# main_6.net
KiCad netlist of a schematic drawn in Altium Designer
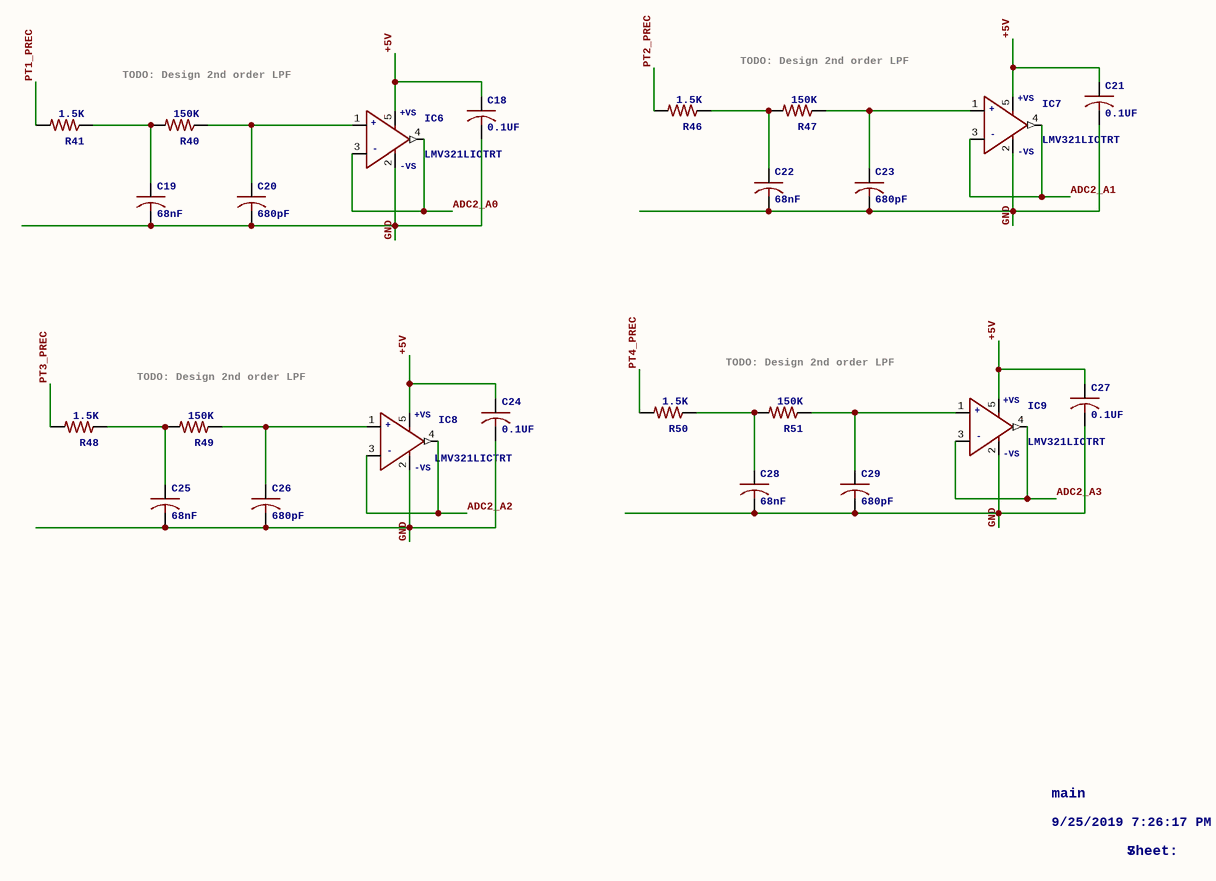
[diagram p0: main_6.SchDoc]

(export (version "E")
  (design (tool "Eeschema 10.0.6"))
  (components
    (comp (ref "C18")
      (value "0.1UF")
      (footprint "C0805")
      (description "CAPACITOR, American symbol")
      (libsource (lib "rcl") (part "C-USC0805"))
    )
    (comp (ref "C19")
      (value "68nF")
      (footprint "C0805")
      (description "CAPACITOR, American symbol")
      (libsource (lib "rcl") (part "C-USC0805"))
    )
    (comp (ref "C20")
      (value "680pF")
      (footprint "C0805")
      (description "CAPACITOR, American symbol")
      (libsource (lib "rcl") (part "C-USC0805"))
    )
    (comp (ref "C21")
      (value "0.1UF")
      (footprint "C0805")
      (description "CAPACITOR, American symbol")
      (libsource (lib "rcl") (part "C-USC0805"))
    )
    (comp (ref "C22")
      (value "68nF")
      (footprint "C0805")
      (description "CAPACITOR, American symbol")
      (libsource (lib "rcl") (part "C-USC0805"))
    )
    (comp (ref "C23")
      (value "680pF")
      (footprint "C0805")
      (description "CAPACITOR, American symbol")
      (libsource (lib "rcl") (part "C-USC0805"))
    )
    (comp (ref "C24")
      (value "0.1UF")
      (footprint "C0805")
      (description "CAPACITOR, American symbol")
      (libsource (lib "rcl") (part "C-USC0805"))
    )
    (comp (ref "C25")
      (value "68nF")
      (footprint "C0805")
      (description "CAPACITOR, American symbol")
      (libsource (lib "rcl") (part "C-USC0805"))
    )
    (comp (ref "C26")
      (value "680pF")
      (footprint "C0805")
      (description "CAPACITOR, American symbol")
      (libsource (lib "rcl") (part "C-USC0805"))
    )
    (comp (ref "C27")
      (value "0.1UF")
      (footprint "C0805")
      (description "CAPACITOR, American symbol")
      (libsource (lib "rcl") (part "C-USC0805"))
    )
    (comp (ref "C28")
      (value "68nF")
      (footprint "C0805")
      (description "CAPACITOR, American symbol")
      (libsource (lib "rcl") (part "C-USC0805"))
    )
    (comp (ref "C29")
      (value "680pF")
      (footprint "C0805")
      (description "CAPACITOR, American symbol")
      (libsource (lib "rcl") (part "C-USC0805"))
    )
    (comp (ref "IC6")
      (value "LMV321LICTRT")
      (footprint "SOT23-5")
      (fields
        (field (name "MF") "ALTERA CORPORATION")
        (field (name "MPN") "AD8065ARTZ-REEL7")
        (field (name "+") "+")
        (field (name "-") "-")
        (field (name "+VS") "+VS")
        (field (name "-VS") "-VS")
        (field (name "LIBRARYNAME") "st-microelectronics-extra")
      )
      (libsource (lib "st-microelectronics-extra") (part "LMV321LICTRT"))
    )
    (comp (ref "IC7")
      (value "LMV321LICTRT")
      (footprint "SOT23-5")
      (fields
        (field (name "MF") "ALTERA CORPORATION")
        (field (name "MPN") "AD8065ARTZ-REEL7")
        (field (name "+") "+")
        (field (name "-") "-")
        (field (name "+VS") "+VS")
        (field (name "-VS") "-VS")
        (field (name "LIBRARYNAME") "st-microelectronics-extra")
      )
      (libsource (lib "st-microelectronics-extra") (part "LMV321LICTRT"))
    )
    (comp (ref "IC8")
      (value "LMV321LICTRT")
      (footprint "SOT23-5")
      (fields
        (field (name "MF") "ALTERA CORPORATION")
        (field (name "MPN") "AD8065ARTZ-REEL7")
        (field (name "+") "+")
        (field (name "-") "-")
        (field (name "+VS") "+VS")
        (field (name "-VS") "-VS")
        (field (name "LIBRARYNAME") "st-microelectronics-extra")
      )
      (libsource (lib "st-microelectronics-extra") (part "LMV321LICTRT"))
    )
    (comp (ref "IC9")
      (value "LMV321LICTRT")
      (footprint "SOT23-5")
      (fields
        (field (name "MF") "ALTERA CORPORATION")
        (field (name "MPN") "AD8065ARTZ-REEL7")
        (field (name "+") "+")
        (field (name "-") "-")
        (field (name "+VS") "+VS")
        (field (name "-VS") "-VS")
        (field (name "LIBRARYNAME") "st-microelectronics-extra")
      )
      (libsource (lib "st-microelectronics-extra") (part "LMV321LICTRT"))
    )
    (comp (ref "R40")
      (value "150K")
      (footprint "R0805")
      (description "RESISTOR, American symbol")
      (libsource (lib "rcl") (part "R-US_R0805"))
    )
    (comp (ref "R41")
      (value "1.5K")
      (footprint "R0805")
      (description "RESISTOR, American symbol")
      (libsource (lib "rcl") (part "R-US_R0805"))
    )
    (comp (ref "R46")
      (value "1.5K")
      (footprint "R0805")
      (description "RESISTOR, American symbol")
      (libsource (lib "rcl") (part "R-US_R0805"))
    )
    (comp (ref "R47")
      (value "150K")
      (footprint "R0805")
      (description "RESISTOR, American symbol")
      (libsource (lib "rcl") (part "R-US_R0805"))
    )
    (comp (ref "R48")
      (value "1.5K")
      (footprint "R0805")
      (description "RESISTOR, American symbol")
      (libsource (lib "rcl") (part "R-US_R0805"))
    )
    (comp (ref "R49")
      (value "150K")
      (footprint "R0805")
      (description "RESISTOR, American symbol")
      (libsource (lib "rcl") (part "R-US_R0805"))
    )
    (comp (ref "R50")
      (value "1.5K")
      (footprint "R0805")
      (description "RESISTOR, American symbol")
      (libsource (lib "rcl") (part "R-US_R0805"))
    )
    (comp (ref "R51")
      (value "150K")
      (footprint "R0805")
      (description "RESISTOR, American symbol")
      (libsource (lib "rcl") (part "R-US_R0805"))
    )
  )
  (nets
    (net (code "1") (name "/+5V") (class "Default")
      (node (ref "C18") (pin "1") (pinfunction "1_1") (pintype "passive"))
      (node (ref "C21") (pin "1") (pinfunction "1_1") (pintype "passive"))
      (node (ref "C24") (pin "1") (pinfunction "1_1") (pintype "passive"))
      (node (ref "C27") (pin "1") (pinfunction "1_1") (pintype "passive"))
      (node (ref "IC6") (pin "5") (pinfunction "+VS_5") (pintype "passive"))
      (node (ref "IC7") (pin "5") (pinfunction "+VS_5") (pintype "passive"))
      (node (ref "IC8") (pin "5") (pinfunction "+VS_5") (pintype "passive"))
      (node (ref "IC9") (pin "5") (pinfunction "+VS_5") (pintype "passive"))
    )
    (net (code "2") (name "/ADC2_A0") (class "Default")
      (node (ref "IC6") (pin "3") (pinfunction "IN-_3") (pintype "passive"))
      (node (ref "IC6") (pin "4") (pinfunction "OUT_4") (pintype "output"))
    )
    (net (code "3") (name "/ADC2_A1") (class "Default")
      (node (ref "IC7") (pin "3") (pinfunction "IN-_3") (pintype "passive"))
      (node (ref "IC7") (pin "4") (pinfunction "OUT_4") (pintype "output"))
    )
    (net (code "4") (name "/ADC2_A2") (class "Default")
      (node (ref "IC8") (pin "3") (pinfunction "IN-_3") (pintype "passive"))
      (node (ref "IC8") (pin "4") (pinfunction "OUT_4") (pintype "output"))
    )
    (net (code "5") (name "/ADC2_A3") (class "Default")
      (node (ref "IC9") (pin "3") (pinfunction "IN-_3") (pintype "passive"))
      (node (ref "IC9") (pin "4") (pinfunction "OUT_4") (pintype "output"))
    )
    (net (code "6") (name "/GND") (class "Default")
      (node (ref "C18") (pin "2") (pinfunction "2_2") (pintype "passive"))
      (node (ref "C19") (pin "2") (pinfunction "2_2") (pintype "passive"))
      (node (ref "C20") (pin "2") (pinfunction "2_2") (pintype "passive"))
      (node (ref "C21") (pin "2") (pinfunction "2_2") (pintype "passive"))
      (node (ref "C22") (pin "2") (pinfunction "2_2") (pintype "passive"))
      (node (ref "C23") (pin "2") (pinfunction "2_2") (pintype "passive"))
      (node (ref "C24") (pin "2") (pinfunction "2_2") (pintype "passive"))
      (node (ref "C25") (pin "2") (pinfunction "2_2") (pintype "passive"))
      (node (ref "C26") (pin "2") (pinfunction "2_2") (pintype "passive"))
      (node (ref "C27") (pin "2") (pinfunction "2_2") (pintype "passive"))
      (node (ref "C28") (pin "2") (pinfunction "2_2") (pintype "passive"))
      (node (ref "C29") (pin "2") (pinfunction "2_2") (pintype "passive"))
      (node (ref "IC6") (pin "2") (pinfunction "-VS_2") (pintype "passive"))
      (node (ref "IC7") (pin "2") (pinfunction "-VS_2") (pintype "passive"))
      (node (ref "IC8") (pin "2") (pinfunction "-VS_2") (pintype "passive"))
      (node (ref "IC9") (pin "2") (pinfunction "-VS_2") (pintype "passive"))
    )
    (net (code "7") (name "/PT1_PREC") (class "Default")
      (node (ref "R41") (pin "2") (pinfunction "2_2") (pintype "passive"))
    )
    (net (code "8") (name "/PT2_PREC") (class "Default")
      (node (ref "R46") (pin "2") (pinfunction "2_2") (pintype "passive"))
    )
    (net (code "9") (name "/PT3_PREC") (class "Default")
      (node (ref "R48") (pin "2") (pinfunction "2_2") (pintype "passive"))
    )
    (net (code "10") (name "/PT4_PREC") (class "Default")
      (node (ref "R50") (pin "2") (pinfunction "2_2") (pintype "passive"))
    )
    (net (code "11") (name "Net-(C19-Pad1)") (class "Default")
      (node (ref "C19") (pin "1") (pinfunction "1_1") (pintype "passive"))
      (node (ref "R40") (pin "2") (pinfunction "2_2") (pintype "passive"))
      (node (ref "R41") (pin "1") (pinfunction "1_1") (pintype "passive"))
    )
    (net (code "12") (name "Net-(C22-Pad1)") (class "Default")
      (node (ref "C22") (pin "1") (pinfunction "1_1") (pintype "passive"))
      (node (ref "R46") (pin "1") (pinfunction "1_1") (pintype "passive"))
      (node (ref "R47") (pin "2") (pinfunction "2_2") (pintype "passive"))
    )
    (net (code "13") (name "Net-(C25-Pad1)") (class "Default")
      (node (ref "C25") (pin "1") (pinfunction "1_1") (pintype "passive"))
      (node (ref "R48") (pin "1") (pinfunction "1_1") (pintype "passive"))
      (node (ref "R49") (pin "2") (pinfunction "2_2") (pintype "passive"))
    )
    (net (code "14") (name "Net-(C28-Pad1)") (class "Default")
      (node (ref "C28") (pin "1") (pinfunction "1_1") (pintype "passive"))
      (node (ref "R50") (pin "1") (pinfunction "1_1") (pintype "passive"))
      (node (ref "R51") (pin "2") (pinfunction "2_2") (pintype "passive"))
    )
    (net (code "15") (name "Net-(IC6-IN+)") (class "Default")
      (node (ref "C20") (pin "1") (pinfunction "1_1") (pintype "passive"))
      (node (ref "IC6") (pin "1") (pinfunction "IN+_1") (pintype "passive"))
      (node (ref "R40") (pin "1") (pinfunction "1_1") (pintype "passive"))
    )
    (net (code "16") (name "Net-(IC7-IN+)") (class "Default")
      (node (ref "C23") (pin "1") (pinfunction "1_1") (pintype "passive"))
      (node (ref "IC7") (pin "1") (pinfunction "IN+_1") (pintype "passive"))
      (node (ref "R47") (pin "1") (pinfunction "1_1") (pintype "passive"))
    )
    (net (code "17") (name "Net-(IC8-IN+)") (class "Default")
      (node (ref "C26") (pin "1") (pinfunction "1_1") (pintype "passive"))
      (node (ref "IC8") (pin "1") (pinfunction "IN+_1") (pintype "passive"))
      (node (ref "R49") (pin "1") (pinfunction "1_1") (pintype "passive"))
    )
    (net (code "18") (name "Net-(IC9-IN+)") (class "Default")
      (node (ref "C29") (pin "1") (pinfunction "1_1") (pintype "passive"))
      (node (ref "IC9") (pin "1") (pinfunction "IN+_1") (pintype "passive"))
      (node (ref "R51") (pin "1") (pinfunction "1_1") (pintype "passive"))
    )
  )
)
